# 12V-5A-buck.net
KiCad netlist of a schematic drawn in Altium Designer
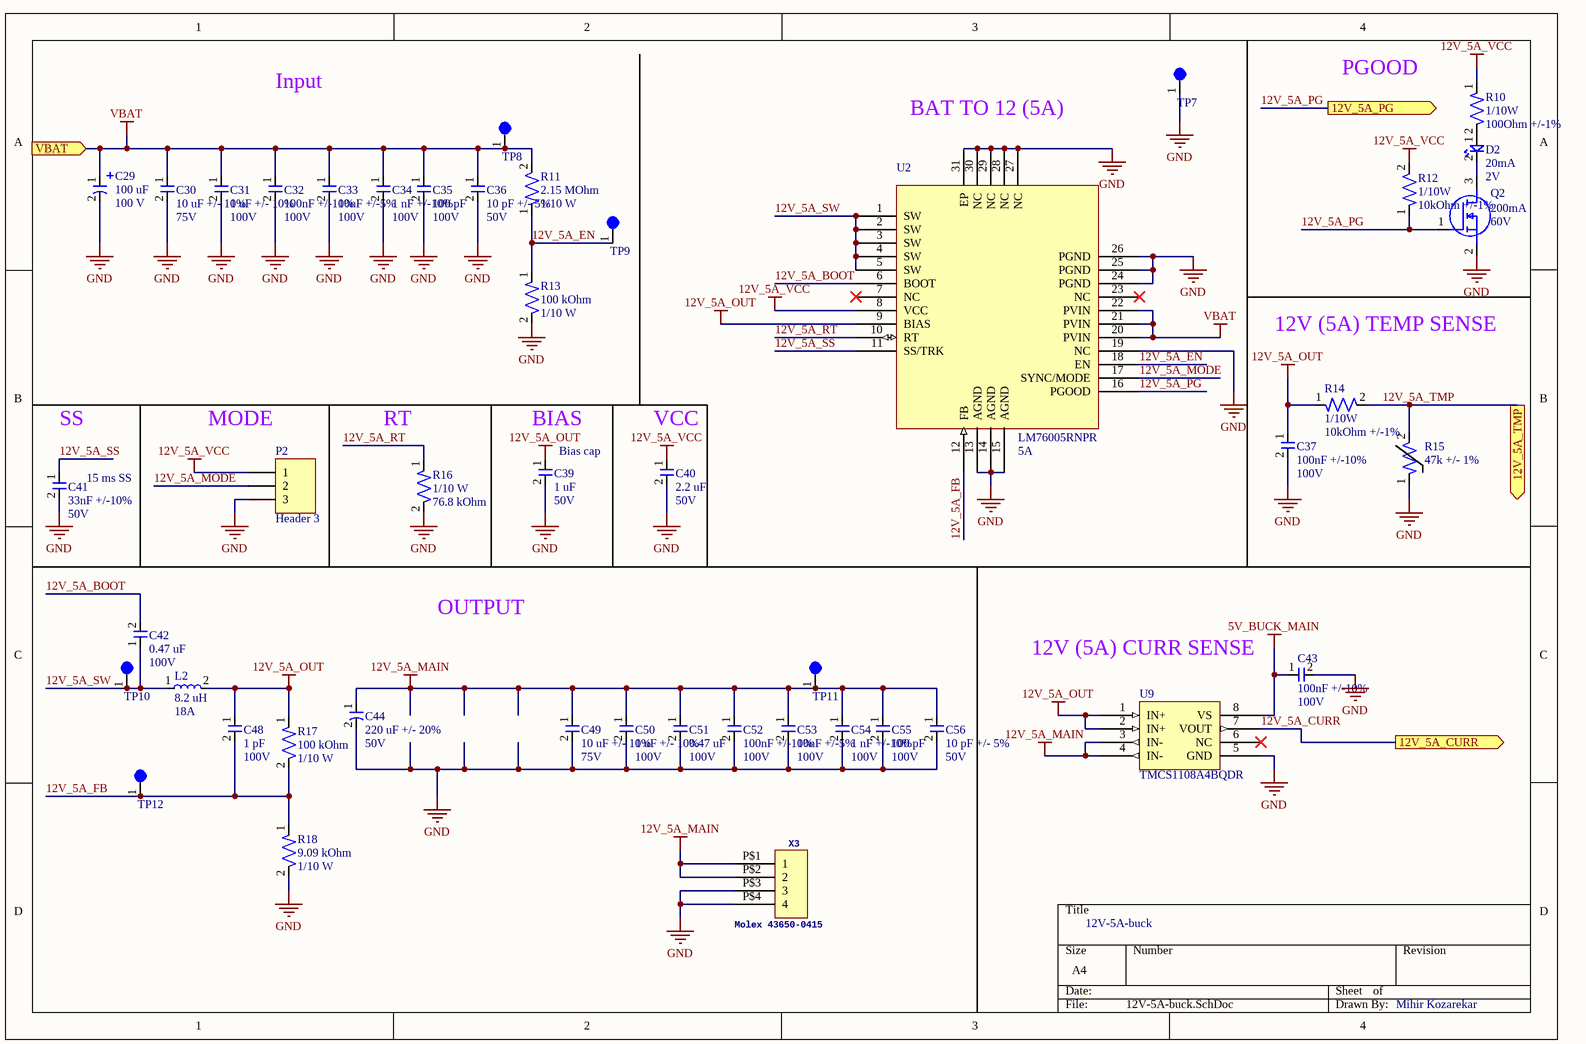
[diagram p0: 12V-5A-buck.SchDoc]

(export (version "E")
  (design (tool "Eeschema 10.0.6"))
  (components
    (comp (ref "C29")
      (value "100SEV100M12.5X16")
      (footprint "ELEC-100U-0001")
      (description "100 µF 100 V Aluminum Electrolytic Capacitors Radial, Can - SMD 2000 Hrs @ 85°C")
      (fields
        (field (name "MANUFACTURER") "Rubycon")
        (field (name "TOLERANCE") "+/- 20%")
        (field (name "CAPACITANCE") "100 uF")
        (field (name "VOLTAGE") "100 V")
      )
      (libsource (lib "MasterLib") (part "ELEC-100U-0001"))
    )
    (comp (ref "C30")
      (value "C3225X7R1N106K250AC")
      (footprint "CAP-1210")
      (description "10 µF ±10% 75V Ceramic Capacitor X7R 1210 (3225 Metric)")
      (fields (field (name "CAPACITANCE") "10 uF +/- 10%") (field (name "VOLTAGE RATING") "75V"))
      (libsource (lib "MasterLib") (part "CAP-10U-0004"))
    )
    (comp (ref "C31")
      (value "CL31B105KCHNNNE")
      (footprint "CAP-1206 - duplicate")
      (description "1 µF ±10% 100V Ceramic Capacitor X7R 1206 (3216 Metric)")
      (fields (field (name "CAPACITANCE") "1 uF +/- 10%") (field (name "VOLTAGE") "100V"))
      (libsource (lib "MasterLib") (part "CAP-1U-0001"))
    )
    (comp (ref "C32")
      (value "CC0603KRX7R0BB104")
      (footprint "CAP-0603")
      (description "CAP CER 0.1UF 100V X7R 0603")
      (fields
        (field (name "MANUFACTURER") "YAGEO")
        (field (name "CAPACITANCE") "100nF +/-10%")
        (field (name "VOLTAGE RATING") "100V")
      )
      (libsource (lib "MasterLib") (part "CAP-100N-0001"))
    )
    (comp (ref "C33")
      (value "C1608C0G2A103J080AC")
      (footprint "CAP-0603")
      (description "CAP CER 10000PF 100V C0G 0603")
      (fields
        (field (name "MANUFACTURER") "TDK Corporation")
        (field (name "CAPACITANCE") "10nF +/-5%")
        (field (name "VOLTAGE RATING") "100V")
      )
      (libsource (lib "MasterLib") (part "CAP-10N-0002"))
    )
    (comp (ref "C34")
      (value "C0603Y102K1RAC7867")
      (footprint "CAP-0603")
      (description "1000 pF ±10% 100V Ceramic Capacitor X7R 0603 (1608 Metric)")
      (fields (field (name "CAPACITANCE") "1 nF +/-10%") (field (name "VOLTAGE") "100V"))
      (libsource (lib "MasterLib") (part "CAP-1N-0001"))
    )
    (comp (ref "C35")
      (value "0603N101J101CT")
      (footprint "CAP-0603")
      (description "100 pF ±5% 100V Ceramic Capacitor C0G, NP0 0603 (1608 Metric)")
      (fields
        (field (name "TOLERANCE") "+/-5%")
        (field (name "CAPACITANCE") "100 pF")
        (field (name "VOLTAGE") "100V")
      )
      (libsource (lib "MasterLib") (part "CAP-100P-0002"))
    )
    (comp (ref "C36")
      (value "0603N100J500CT")
      (footprint "CAP-0603")
      (description "10 pF ±5% 50V Ceramic Capacitor C0G, NP0 0603 (1608 Metric)")
      (fields
        (field (name "MANUFACTURER") "Walshin Technology Corporation")
        (field (name "CAPACITANCE") "10 pF +/- 5%")
        (field (name "VOLTAGE RATING") "50V")
      )
      (libsource (lib "MasterLib") (part "CAP-10P-0001"))
    )
    (comp (ref "C37")
      (value "CC0603KRX7R0BB104")
      (footprint "CAP-0603")
      (description "CAP CER 0.1UF 100V X7R 0603")
      (fields
        (field (name "MANUFACTURER") "YAGEO")
        (field (name "CAPACITANCE") "100nF +/-10%")
        (field (name "VOLTAGE RATING") "100V")
      )
      (libsource (lib "MasterLib") (part "CAP-100N-0001"))
    )
    (comp (ref "C39")
      (value "UMK107AB7105KA-T")
      (footprint "CAP-0603")
      (description "1 µF ±10% 50V Ceramic Capacitor X7R 0603 (1608 Metric)")
      (fields (field (name "CAPACITANCE") "1 uF") (field (name "VOLTAGE") "50V"))
      (libsource (lib "MasterLib") (part "CAP-1U-0002"))
    )
    (comp (ref "C40")
      (value "UMK107BBJ225KA-T")
      (footprint "CAP-0603")
      (description "2.2 µF ±10% 50V Ceramic Capacitor X5R 0603 (1608 Metric)")
      (fields (field (name "CAPACITANCE") "2.2 uF") (field (name "OLTAGE") "50V"))
      (libsource (lib "MasterLib") (part "CAP-2.2U-0001"))
    )
    (comp (ref "C41")
      (value "CC0603KRX7R9BB333")
      (footprint "CAP-0603")
      (description "0.033 µF ±10% 50V Ceramic Capacitor X7R 0603 (1608 Metric)")
      (fields
        (field (name "MANUFACTURER") "YAGEO")
        (field (name "CAPACITANCE") "33nF +/-10%")
        (field (name "VOLTAGE RATING") "50V")
      )
      (libsource (lib "MasterLib") (part "CAP-33N-0001"))
    )
    (comp (ref "C42")
      (value "KAM21KR72A474KL")
      (footprint "CAP-0805")
      (description "0.47 µF ±10% 100V Ceramic Capacitor X7R 0805 (2012 Metric)")
      (fields
        (field (name "TOLERANCE") "+/- 10%")
        (field (name "CAPACITANCE") "0.47 uF")
        (field (name "VOLTAGE") "100V")
      )
      (libsource (lib "MasterLib") (part "CAP-0.47U-0001"))
    )
    (comp (ref "C43")
      (value "CC0603KRX7R0BB104")
      (footprint "CAP-0603")
      (description "CAP CER 0.1UF 100V X7R 0603")
      (fields
        (field (name "MANUFACTURER") "YAGEO")
        (field (name "CAPACITANCE") "100nF +/-10%")
        (field (name "VOLTAGE RATING") "100V")
      )
      (libsource (lib "MasterLib") (part "CAP-100N-0001"))
    )
    (comp (ref "C44")
      (value "50TZV220M10X10.5")
      (footprint "ELEC-220U-0003")
      (description "220 µF 50 V Aluminum Electrolytic Capacitors Radial, Can - SMD 2000 Hrs @ 105°C")
      (fields (field (name "CAPACITANCE") "220 uF +/- 20%") (field (name "VOLTAGE RATING") "50V"))
      (libsource (lib "MasterLib") (part "ELEC-220U-0003"))
    )
    (comp (ref "C48")
      (value "885012006087")
      (footprint "CAP-0603")
      (description "1 pF ±0.25pF 100V Ceramic Capacitor C0G, NP0 0603 (1608 Metric)")
      (fields
        (field (name "TOLERANCE") "+/- 0.25 pF")
        (field (name "CAPACITANCE") "1 pF")
        (field (name "VOLTAGE") "100V")
      )
      (libsource (lib "MasterLib") (part "CAP-1P-0001"))
    )
    (comp (ref "C49")
      (value "C3225X7R1N106K250AC")
      (footprint "CAP-1210")
      (description "10 µF ±10% 75V Ceramic Capacitor X7R 1210 (3225 Metric)")
      (fields (field (name "CAPACITANCE") "10 uF +/- 10%") (field (name "VOLTAGE RATING") "75V"))
      (libsource (lib "MasterLib") (part "CAP-10U-0004"))
    )
    (comp (ref "C50")
      (value "CL31B105KCHNNNE")
      (footprint "CAP-1206 - duplicate")
      (description "1 µF ±10% 100V Ceramic Capacitor X7R 1206 (3216 Metric)")
      (fields (field (name "CAPACITANCE") "1 uF +/- 10%") (field (name "VOLTAGE") "100V"))
      (libsource (lib "MasterLib") (part "CAP-1U-0001"))
    )
    (comp (ref "C51")
      (value "KAM21KR72A474KL")
      (footprint "CAP-0805")
      (description "0.47 µF ±10% 100V Ceramic Capacitor X7R 0805 (2012 Metric)")
      (fields
        (field (name "TOLERANCE") "+/- 10%")
        (field (name "CAPACITANCE") "0.47 uF")
        (field (name "VOLTAGE") "100V")
      )
      (libsource (lib "MasterLib") (part "CAP-0.47U-0001"))
    )
    (comp (ref "C52")
      (value "CC0603KRX7R0BB104")
      (footprint "CAP-0603")
      (description "CAP CER 0.1UF 100V X7R 0603")
      (fields
        (field (name "MANUFACTURER") "YAGEO")
        (field (name "CAPACITANCE") "100nF +/-10%")
        (field (name "VOLTAGE RATING") "100V")
      )
      (libsource (lib "MasterLib") (part "CAP-100N-0001"))
    )
    (comp (ref "C53")
      (value "C1608C0G2A103J080AC")
      (footprint "CAP-0603")
      (description "CAP CER 10000PF 100V C0G 0603")
      (fields
        (field (name "MANUFACTURER") "TDK Corporation")
        (field (name "CAPACITANCE") "10nF +/-5%")
        (field (name "VOLTAGE RATING") "100V")
      )
      (libsource (lib "MasterLib") (part "CAP-10N-0002"))
    )
    (comp (ref "C54")
      (value "C0603Y102K1RAC7867")
      (footprint "CAP-0603")
      (description "1000 pF ±10% 100V Ceramic Capacitor X7R 0603 (1608 Metric)")
      (fields (field (name "CAPACITANCE") "1 nF +/-10%") (field (name "VOLTAGE") "100V"))
      (libsource (lib "MasterLib") (part "CAP-1N-0001"))
    )
    (comp (ref "C55")
      (value "0603N101J101CT")
      (footprint "CAP-0603")
      (description "100 pF ±5% 100V Ceramic Capacitor C0G, NP0 0603 (1608 Metric)")
      (fields
        (field (name "TOLERANCE") "+/-5%")
        (field (name "CAPACITANCE") "100 pF")
        (field (name "VOLTAGE") "100V")
      )
      (libsource (lib "MasterLib") (part "CAP-100P-0002"))
    )
    (comp (ref "C56")
      (value "0603N100J500CT")
      (footprint "CAP-0603")
      (description "10 pF ±5% 50V Ceramic Capacitor C0G, NP0 0603 (1608 Metric)")
      (fields
        (field (name "MANUFACTURER") "Walshin Technology Corporation")
        (field (name "CAPACITANCE") "10 pF +/- 5%")
        (field (name "VOLTAGE RATING") "50V")
      )
      (libsource (lib "MasterLib") (part "CAP-10P-0001"))
    )
    (comp (ref "D2")
      (value "150060AS75000")
      (footprint "LED-0603")
      (description "CAP CER 0.1UF 100V X7R 0603")
      (fields
        (field (name "MANUFACTURER") "Wurth Electronik")
        (field (name "CURRENT RATING") "20mA")
        (field (name "VF") "2V")
      )
      (libsource (lib "MasterLib") (part "LED_Amber_0001"))
    )
    (comp (ref "L2")
      (value "IHLP6767GZER8R2M01")
      (footprint "PWRIND-8.2U-0002")
      (description "8.2 µH Shielded Molded Inductor 18 A 10.66mOhm Max Nonstandard")
      (fields
        (field (name "TOLERANCE") "+/-20%")
        (field (name "INDUCTANCE") "8.2 uH")
        (field (name "DCI") "18A")
      )
      (libsource (lib "MasterLib") (part "PWRIND-8.2U-0002"))
    )
    (comp (ref "P2")
      (value "Header 3")
      (footprint "HDR1X3")
      (description "Header, 3-Pin")
      (fields (field (name "PUBLISHER") "Altium Limited"))
      (libsource (lib "Miscellaneous Connectors") (part "Header 3"))
    )
    (comp (ref "Q2")
      (value "T2N7002AK,LM")
      (footprint "NMOS-SOT23-3")
      (description "MOSFET N-CH 60V 200MA SOT23")
      (fields
        (field (name "MANUFACTURER") "Toshiba")
        (field (name "ID-CONTINUOUS") "200mA")
        (field (name "VDS-MAX") "60V")
      )
      (libsource (lib "MasterLib") (part "NMOS-200MA-0001"))
    )
    (comp (ref "R10")
      (value "AC0603FR-10100RL")
      (footprint "RES-0603")
      (description "100 Ohms ±1% 0.1W, 1/10W Chip Resistor 0603 (1608 Metric) Automotive AEC-Q200 Thick Film")
      (fields
        (field (name "MANUFACTURER") "YAGEO")
        (field (name "POWER RATING") "1/10W")
        (field (name "RESISTANCE") "100Ohm +/-1%")
      )
      (libsource (lib "MasterLib") (part "RES-100-0002"))
    )
    (comp (ref "R11")
      (value "RC0603FR-072M15L")
      (footprint "RES-0603")
      (description "2.15 MOhms ±1% 0.1W, 1/10W Chip Resistor 0603 (1608 Metric) Moisture Resistant Thick Film")
      (fields
        (field (name "TOLERANCE") "+/-1%")
        (field (name "RESISTANCE") "2.15 MOhm")
        (field (name "POWER") "1/10 W")
      )
      (libsource (lib "MasterLib") (part "RES-2.15M-0001"))
    )
    (comp (ref "R12")
      (value "RC0603FR-0710KP")
      (footprint "RES-0603")
      (description "RES SMD 10K OHM 1% 1/10W 0603")
      (fields
        (field (name "MANUFACTURER") "YAGEO")
        (field (name "POWER RATING") "1/10W")
        (field (name "RESISTANCE") "10kOhm +/-1%")
      )
      (libsource (lib "MasterLib") (part "RES-10K-0002"))
    )
    (comp (ref "R13")
      (value "RC0603FR-07100KL")
      (footprint "RES-0603")
      (description "100 kOhms ±1% 0.1W, 1/10W Chip Resistor 0603 (1608 Metric) Moisture Resistant Thick Film")
      (fields
        (field (name "TOLERANCE") "+/- 1%")
        (field (name "RESISTANCE") "100 kOhm")
        (field (name "POWER") "1/10 W")
      )
      (libsource (lib "MasterLib") (part "RES-100K-0003"))
    )
    (comp (ref "R14")
      (value "RC0603FR-0710KP")
      (footprint "RES-0603")
      (description "RES SMD 10K OHM 1% 1/10W 0603")
      (fields
        (field (name "MANUFACTURER") "YAGEO")
        (field (name "POWER RATING") "1/10W")
        (field (name "RESISTANCE") "10kOhm +/-1%")
      )
      (libsource (lib "MasterLib") (part "RES-10K-0002"))
    )
    (comp (ref "R15")
      (value "TMP6431DECR")
      (footprint "RES-0402")
      (description "PTC Thermistor 47 kOhms 0402 (1006 Metric)")
      (fields (field (name "MANUFACTURER") "Texas Instruments") (field (name "RESISTANCE") "47k +/- 1%"))
      (libsource (lib "MasterLib") (part "THERM-47K-0001"))
    )
    (comp (ref "R16")
      (value "RC0603FR-0776K8L")
      (footprint "RES-0603")
      (description "76.8 kOhms ±1% 0.1W, 1/10W Chip Resistor 0603 (1608 Metric) Moisture Resistant Thick Film")
      (fields
        (field (name "MANUFACTURER") "Yageo")
        (field (name "TOLERANCE") "+/- 1%")
        (field (name "POWER") "1/10 W")
        (field (name "RESISTANCE") "76.8 kOhm")
      )
      (libsource (lib "MasterLib") (part "RES-76.8K-0001"))
    )
    (comp (ref "R17")
      (value "RC0603FR-07100KL")
      (footprint "RES-0603")
      (description "100 kOhms ±1% 0.1W, 1/10W Chip Resistor 0603 (1608 Metric) Moisture Resistant Thick Film")
      (fields
        (field (name "TOLERANCE") "+/- 1%")
        (field (name "RESISTANCE") "100 kOhm")
        (field (name "POWER") "1/10 W")
      )
      (libsource (lib "MasterLib") (part "RES-100K-0003"))
    )
    (comp (ref "R18")
      (value "RC0603FR-079K09L")
      (footprint "RES-0603")
      (description "9.09 kOhms ±1% 0.1W, 1/10W Chip Resistor 0603 (1608 Metric) Moisture Resistant Thick Film")
      (fields
        (field (name "TOLERANCE") "+/-1%")
        (field (name "RESISTANCE") "9.09 kOhm")
        (field (name "POWER") "1/10 W")
      )
      (libsource (lib "MasterLib") (part "RES-9.09K-0001"))
    )
    (comp (ref "TP7")
      (value "5003")
      (footprint "TEST-POINT-0001")
      (description "Oranange PC Test Point, Miniature Phoisphor Bronze Silver Plating Through Hole Mounting Type")
      (libsource (lib "MasterLib") (part "TEST-POINT-0001"))
    )
    (comp (ref "TP8")
      (value "5003")
      (footprint "TEST-POINT-0001")
      (description "Oranange PC Test Point, Miniature Phoisphor Bronze Silver Plating Through Hole Mounting Type")
      (libsource (lib "MasterLib") (part "TEST-POINT-0001"))
    )
    (comp (ref "TP9")
      (value "5003")
      (footprint "TEST-POINT-0001")
      (description "Oranange PC Test Point, Miniature Phoisphor Bronze Silver Plating Through Hole Mounting Type")
      (libsource (lib "MasterLib") (part "TEST-POINT-0001"))
    )
    (comp (ref "TP10")
      (value "5003")
      (footprint "TEST-POINT-0001")
      (description "Oranange PC Test Point, Miniature Phoisphor Bronze Silver Plating Through Hole Mounting Type")
      (libsource (lib "MasterLib") (part "TEST-POINT-0001"))
    )
    (comp (ref "TP11")
      (value "5003")
      (footprint "TEST-POINT-0001")
      (description "Oranange PC Test Point, Miniature Phoisphor Bronze Silver Plating Through Hole Mounting Type")
      (libsource (lib "MasterLib") (part "TEST-POINT-0001"))
    )
    (comp (ref "TP12")
      (value "5003")
      (footprint "TEST-POINT-0001")
      (description "Oranange PC Test Point, Miniature Phoisphor Bronze Silver Plating Through Hole Mounting Type")
      (libsource (lib "MasterLib") (part "TEST-POINT-0001"))
    )
    (comp (ref "U2")
      (value "LM76005RNPR")
      (footprint "IC-30-WQFN(6x4)")
      (description "Buck Switching Regulator IC Positive Adjustable 1V 1 Output 5A 30-WFQFN Exposed Pad")
      (fields (field (name "MANUFACTURER") "Texas Instruments") (field (name "CURRENT") "5A"))
      (libsource (lib "MasterLib") (part "IC-BUCK-0006"))
    )
    (comp (ref "U9")
      (value "TMCS1108A4BQDR")
      (footprint "IC-CURRENT-0001")
      (description "Current Sensor 1 Channel Hall Effect Bidirectional 8-SOIC (0.154\", 3.90mm Width)")
      (libsource (lib "MasterLib") (part "IC-CURRENT-0004"))
    )
    (comp (ref "X3")
      (value "Molex 43650-0415")
      (footprint "43650-0415")
      (libsource (lib "Molex Microfit") (part "Micro-Fit Molex 4 Pin Vertical"))
    )
  )
  (nets
    (net (code "1") (name "/12V_5A_BOOT") (class "Default")
      (node (ref "C42") (pin "2") (pinfunction "2_2") (pintype "passive"))
      (node (ref "U2") (pin "6") (pinfunction "BOOT_6") (pintype "power_in"))
    )
    (net (code "2") (name "/12V_5A_CURR") (class "Default")
      (node (ref "U9") (pin "7") (pinfunction "VOUT_7") (pintype "output"))
    )
    (net (code "3") (name "/12V_5A_EN") (class "Default")
      (node (ref "R11") (pin "1") (pinfunction "1_1") (pintype "passive"))
      (node (ref "R13") (pin "1") (pinfunction "1_1") (pintype "passive"))
      (node (ref "TP9") (pin "1") (pinfunction "0_1") (pintype "passive"))
      (node (ref "U2") (pin "18") (pinfunction "EN_18") (pintype "power_in"))
    )
    (net (code "4") (name "/12V_5A_FB") (class "Default")
      (node (ref "C48") (pin "2") (pinfunction "2_2") (pintype "passive"))
      (node (ref "R17") (pin "2") (pinfunction "2_2") (pintype "passive"))
      (node (ref "R18") (pin "1") (pinfunction "1_1") (pintype "passive"))
      (node (ref "TP12") (pin "1") (pinfunction "0_1") (pintype "passive"))
      (node (ref "U2") (pin "12") (pinfunction "FB_12") (pintype "input"))
    )
    (net (code "5") (name "/12V_5A_MODE") (class "Default")
      (node (ref "P2") (pin "2") (pinfunction "2_2") (pintype "passive"))
      (node (ref "U2") (pin "17") (pinfunction "SYNC/MODE_17") (pintype "power_in"))
    )
    (net (code "6") (name "/12V_5A_PG") (class "Default")
      (node (ref "Q2") (pin "1") (pinfunction "G_1") (pintype "passive"))
      (node (ref "R12") (pin "1") (pinfunction "1_1") (pintype "passive"))
      (node (ref "U2") (pin "16") (pinfunction "PGOOD_16") (pintype "power_in"))
    )
    (net (code "7") (name "/12V_5A_RT") (class "Default")
      (node (ref "R16") (pin "1") (pinfunction "1_1") (pintype "passive"))
      (node (ref "U2") (pin "10") (pinfunction "RT_10") (pintype "bidirectional"))
    )
    (net (code "8") (name "/12V_5A_SS") (class "Default")
      (node (ref "C41") (pin "1") (pinfunction "1_1") (pintype "passive"))
      (node (ref "U2") (pin "11") (pinfunction "SS/TRK_11") (pintype "passive"))
    )
    (net (code "9") (name "/12V_5A_SW") (class "Default")
      (node (ref "C42") (pin "1") (pinfunction "1_1") (pintype "passive"))
      (node (ref "L2") (pin "1") (pinfunction "1_1") (pintype "passive"))
      (node (ref "TP10") (pin "1") (pinfunction "0_1") (pintype "passive"))
      (node (ref "U2") (pin "1") (pinfunction "SW_1") (pintype "power_in"))
      (node (ref "U2") (pin "2") (pinfunction "SW_2") (pintype "power_in"))
      (node (ref "U2") (pin "3") (pinfunction "SW_3") (pintype "power_in"))
      (node (ref "U2") (pin "4") (pinfunction "SW_4") (pintype "power_in"))
      (node (ref "U2") (pin "5") (pinfunction "SW_5") (pintype "power_in"))
    )
    (net (code "10") (name "/12V_5A_TMP") (class "Default")
      (node (ref "R14") (pin "2") (pinfunction "2_2") (pintype "passive"))
      (node (ref "R15") (pin "2") (pinfunction "2_2") (pintype "passive"))
    )
    (net (code "11") (name "5V_BUCK_MAIN") (class "Default")
      (node (ref "C43") (pin "1") (pinfunction "1_1") (pintype "passive"))
      (node (ref "U9") (pin "8") (pinfunction "VS_8") (pintype "power_in"))
    )
    (net (code "12") (name "12V_5A_MAIN") (class "Default")
      (node (ref "C44") (pin "1") (pinfunction "1_1") (pintype "passive"))
      (node (ref "C49") (pin "1") (pinfunction "1_1") (pintype "passive"))
      (node (ref "C50") (pin "1") (pinfunction "1_1") (pintype "passive"))
      (node (ref "C51") (pin "1") (pinfunction "1_1") (pintype "passive"))
      (node (ref "C52") (pin "1") (pinfunction "1_1") (pintype "passive"))
      (node (ref "C53") (pin "1") (pinfunction "1_1") (pintype "passive"))
      (node (ref "C54") (pin "1") (pinfunction "1_1") (pintype "passive"))
      (node (ref "C55") (pin "1") (pinfunction "1_1") (pintype "passive"))
      (node (ref "C56") (pin "1") (pinfunction "1_1") (pintype "passive"))
      (node (ref "TP11") (pin "1") (pinfunction "0_1") (pintype "passive"))
      (node (ref "U9") (pin "3") (pinfunction "IN-_3") (pintype "output"))
      (node (ref "U9") (pin "4") (pinfunction "IN-_4") (pintype "output"))
      (node (ref "X3") (pin "P$1") (pinfunction "1_P$1") (pintype "passive"))
      (node (ref "X3") (pin "P$2") (pinfunction "2_P$2") (pintype "passive"))
    )
    (net (code "13") (name "12V_5A_OUT") (class "Default")
      (node (ref "C37") (pin "1") (pinfunction "1_1") (pintype "passive"))
      (node (ref "C39") (pin "1") (pinfunction "1_1") (pintype "passive"))
      (node (ref "C48") (pin "1") (pinfunction "1_1") (pintype "passive"))
      (node (ref "L2") (pin "2") (pinfunction "2_2") (pintype "passive"))
      (node (ref "R14") (pin "1") (pinfunction "1_1") (pintype "passive"))
      (node (ref "R17") (pin "1") (pinfunction "1_1") (pintype "passive"))
      (node (ref "U2") (pin "9") (pinfunction "BIAS_9") (pintype "power_in"))
      (node (ref "U9") (pin "1") (pinfunction "IN+_1") (pintype "input"))
      (node (ref "U9") (pin "2") (pinfunction "IN+_2") (pintype "input"))
    )
    (net (code "14") (name "12V_5A_VCC") (class "Default")
      (node (ref "C40") (pin "1") (pinfunction "1_1") (pintype "passive"))
      (node (ref "P2") (pin "1") (pinfunction "1_1") (pintype "passive"))
      (node (ref "R10") (pin "1") (pinfunction "1_1") (pintype "passive"))
      (node (ref "R12") (pin "2") (pinfunction "2_2") (pintype "passive"))
      (node (ref "U2") (pin "8") (pinfunction "VCC_8") (pintype "power_in"))
    )
    (net (code "15") (name "GND") (class "Default")
      (node (ref "C29") (pin "2") (pinfunction "2_2") (pintype "passive"))
      (node (ref "C30") (pin "2") (pinfunction "2_2") (pintype "passive"))
      (node (ref "C31") (pin "2") (pinfunction "2_2") (pintype "passive"))
      (node (ref "C32") (pin "2") (pinfunction "2_2") (pintype "passive"))
      (node (ref "C33") (pin "2") (pinfunction "2_2") (pintype "passive"))
      (node (ref "C34") (pin "2") (pinfunction "2_2") (pintype "passive"))
      (node (ref "C35") (pin "2") (pinfunction "2_2") (pintype "passive"))
      (node (ref "C36") (pin "2") (pinfunction "2_2") (pintype "passive"))
      (node (ref "C37") (pin "2") (pinfunction "2_2") (pintype "passive"))
      (node (ref "C39") (pin "2") (pinfunction "2_2") (pintype "passive"))
      (node (ref "C40") (pin "2") (pinfunction "2_2") (pintype "passive"))
      (node (ref "C41") (pin "2") (pinfunction "2_2") (pintype "passive"))
      (node (ref "C43") (pin "2") (pinfunction "2_2") (pintype "passive"))
      (node (ref "C44") (pin "2") (pinfunction "2_2") (pintype "passive"))
      (node (ref "C49") (pin "2") (pinfunction "2_2") (pintype "passive"))
      (node (ref "C50") (pin "2") (pinfunction "2_2") (pintype "passive"))
      (node (ref "C51") (pin "2") (pinfunction "2_2") (pintype "passive"))
      (node (ref "C52") (pin "2") (pinfunction "2_2") (pintype "passive"))
      (node (ref "C53") (pin "2") (pinfunction "2_2") (pintype "passive"))
      (node (ref "C54") (pin "2") (pinfunction "2_2") (pintype "passive"))
      (node (ref "C55") (pin "2") (pinfunction "2_2") (pintype "passive"))
      (node (ref "C56") (pin "2") (pinfunction "2_2") (pintype "passive"))
      (node (ref "P2") (pin "3") (pinfunction "3_3") (pintype "passive"))
      (node (ref "Q2") (pin "2") (pinfunction "S_2") (pintype "passive"))
      (node (ref "R13") (pin "2") (pinfunction "2_2") (pintype "passive"))
      (node (ref "R15") (pin "1") (pinfunction "1_1") (pintype "passive"))
      (node (ref "R16") (pin "2") (pinfunction "2_2") (pintype "passive"))
      (node (ref "R18") (pin "2") (pinfunction "2_2") (pintype "passive"))
      (node (ref "TP7") (pin "1") (pinfunction "0_1") (pintype "passive"))
      (node (ref "U2") (pin "13") (pinfunction "AGND_13") (pintype "power_in"))
      (node (ref "U2") (pin "14") (pinfunction "AGND_14") (pintype "power_in"))
      (node (ref "U2") (pin "15") (pinfunction "AGND_15") (pintype "power_in"))
      (node (ref "U2") (pin "19") (pinfunction "NC_19") (pintype "power_in"))
      (node (ref "U2") (pin "24") (pinfunction "PGND_24") (pintype "power_in"))
      (node (ref "U2") (pin "25") (pinfunction "PGND_25") (pintype "power_in"))
      (node (ref "U2") (pin "26") (pinfunction "PGND_26") (pintype "power_in"))
      (node (ref "U2") (pin "27") (pinfunction "NC_27") (pintype "power_in"))
      (node (ref "U2") (pin "28") (pinfunction "NC_28") (pintype "power_in"))
      (node (ref "U2") (pin "29") (pinfunction "NC_29") (pintype "power_in"))
      (node (ref "U2") (pin "30") (pinfunction "NC_30") (pintype "power_in"))
      (node (ref "U2") (pin "31") (pinfunction "EP_31") (pintype "power_in"))
      (node (ref "U9") (pin "5") (pinfunction "GND_5") (pintype "power_in"))
      (node (ref "X3") (pin "P$3") (pinfunction "3_P$3") (pintype "passive"))
      (node (ref "X3") (pin "P$4") (pinfunction "4_P$4") (pintype "passive"))
    )
    (net (code "16") (name "Net-(D2-Pad1)") (class "Default")
      (node (ref "D2") (pin "1") (pinfunction "1_1") (pintype "passive"))
      (node (ref "R10") (pin "2") (pinfunction "2_2") (pintype "passive"))
    )
    (net (code "17") (name "Net-(Q2-D)") (class "Default")
      (node (ref "D2") (pin "2") (pinfunction "2_2") (pintype "passive"))
      (node (ref "Q2") (pin "3") (pinfunction "D_3") (pintype "passive"))
    )
    (net (code "18") (name "VBAT") (class "Default")
      (node (ref "C29") (pin "1") (pinfunction "1_1") (pintype "passive"))
      (node (ref "C30") (pin "1") (pinfunction "1_1") (pintype "passive"))
      (node (ref "C31") (pin "1") (pinfunction "1_1") (pintype "passive"))
      (node (ref "C32") (pin "1") (pinfunction "1_1") (pintype "passive"))
      (node (ref "C33") (pin "1") (pinfunction "1_1") (pintype "passive"))
      (node (ref "C34") (pin "1") (pinfunction "1_1") (pintype "passive"))
      (node (ref "C35") (pin "1") (pinfunction "1_1") (pintype "passive"))
      (node (ref "C36") (pin "1") (pinfunction "1_1") (pintype "passive"))
      (node (ref "R11") (pin "2") (pinfunction "2_2") (pintype "passive"))
      (node (ref "TP8") (pin "1") (pinfunction "0_1") (pintype "passive"))
      (node (ref "U2") (pin "20") (pinfunction "PVIN_20") (pintype "power_in"))
      (node (ref "U2") (pin "21") (pinfunction "PVIN_21") (pintype "power_in"))
      (node (ref "U2") (pin "22") (pinfunction "PVIN_22") (pintype "power_in"))
    )
    (net (code "19") (name "unconnected-(U2-NC-Pad7)") (class "Default")
      (node (ref "U2") (pin "7") (pinfunction "NC_7") (pintype "power_in+no_connect"))
    )
    (net (code "20") (name "unconnected-(U2-NC-Pad23)") (class "Default")
      (node (ref "U2") (pin "23") (pinfunction "NC_23") (pintype "tri_state+no_connect"))
    )
    (net (code "21") (name "unconnected-(U9-NC-Pad6)") (class "Default")
      (node (ref "U9") (pin "6") (pinfunction "NC_6") (pintype "tri_state+no_connect"))
    )
  )
)
